# CouchProtato-TOP.net
KiCad netlist of a schematic drawn in EAGLE
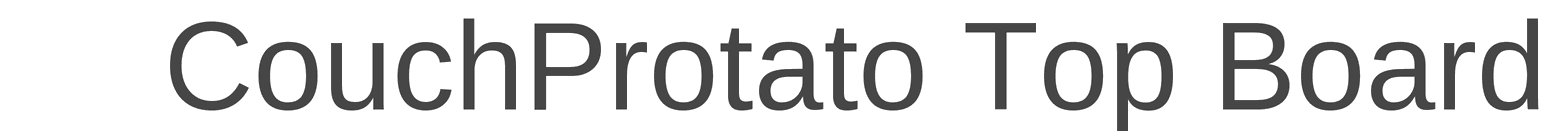
[diagram p0: schematic, sheet 1, part 1 of 2]
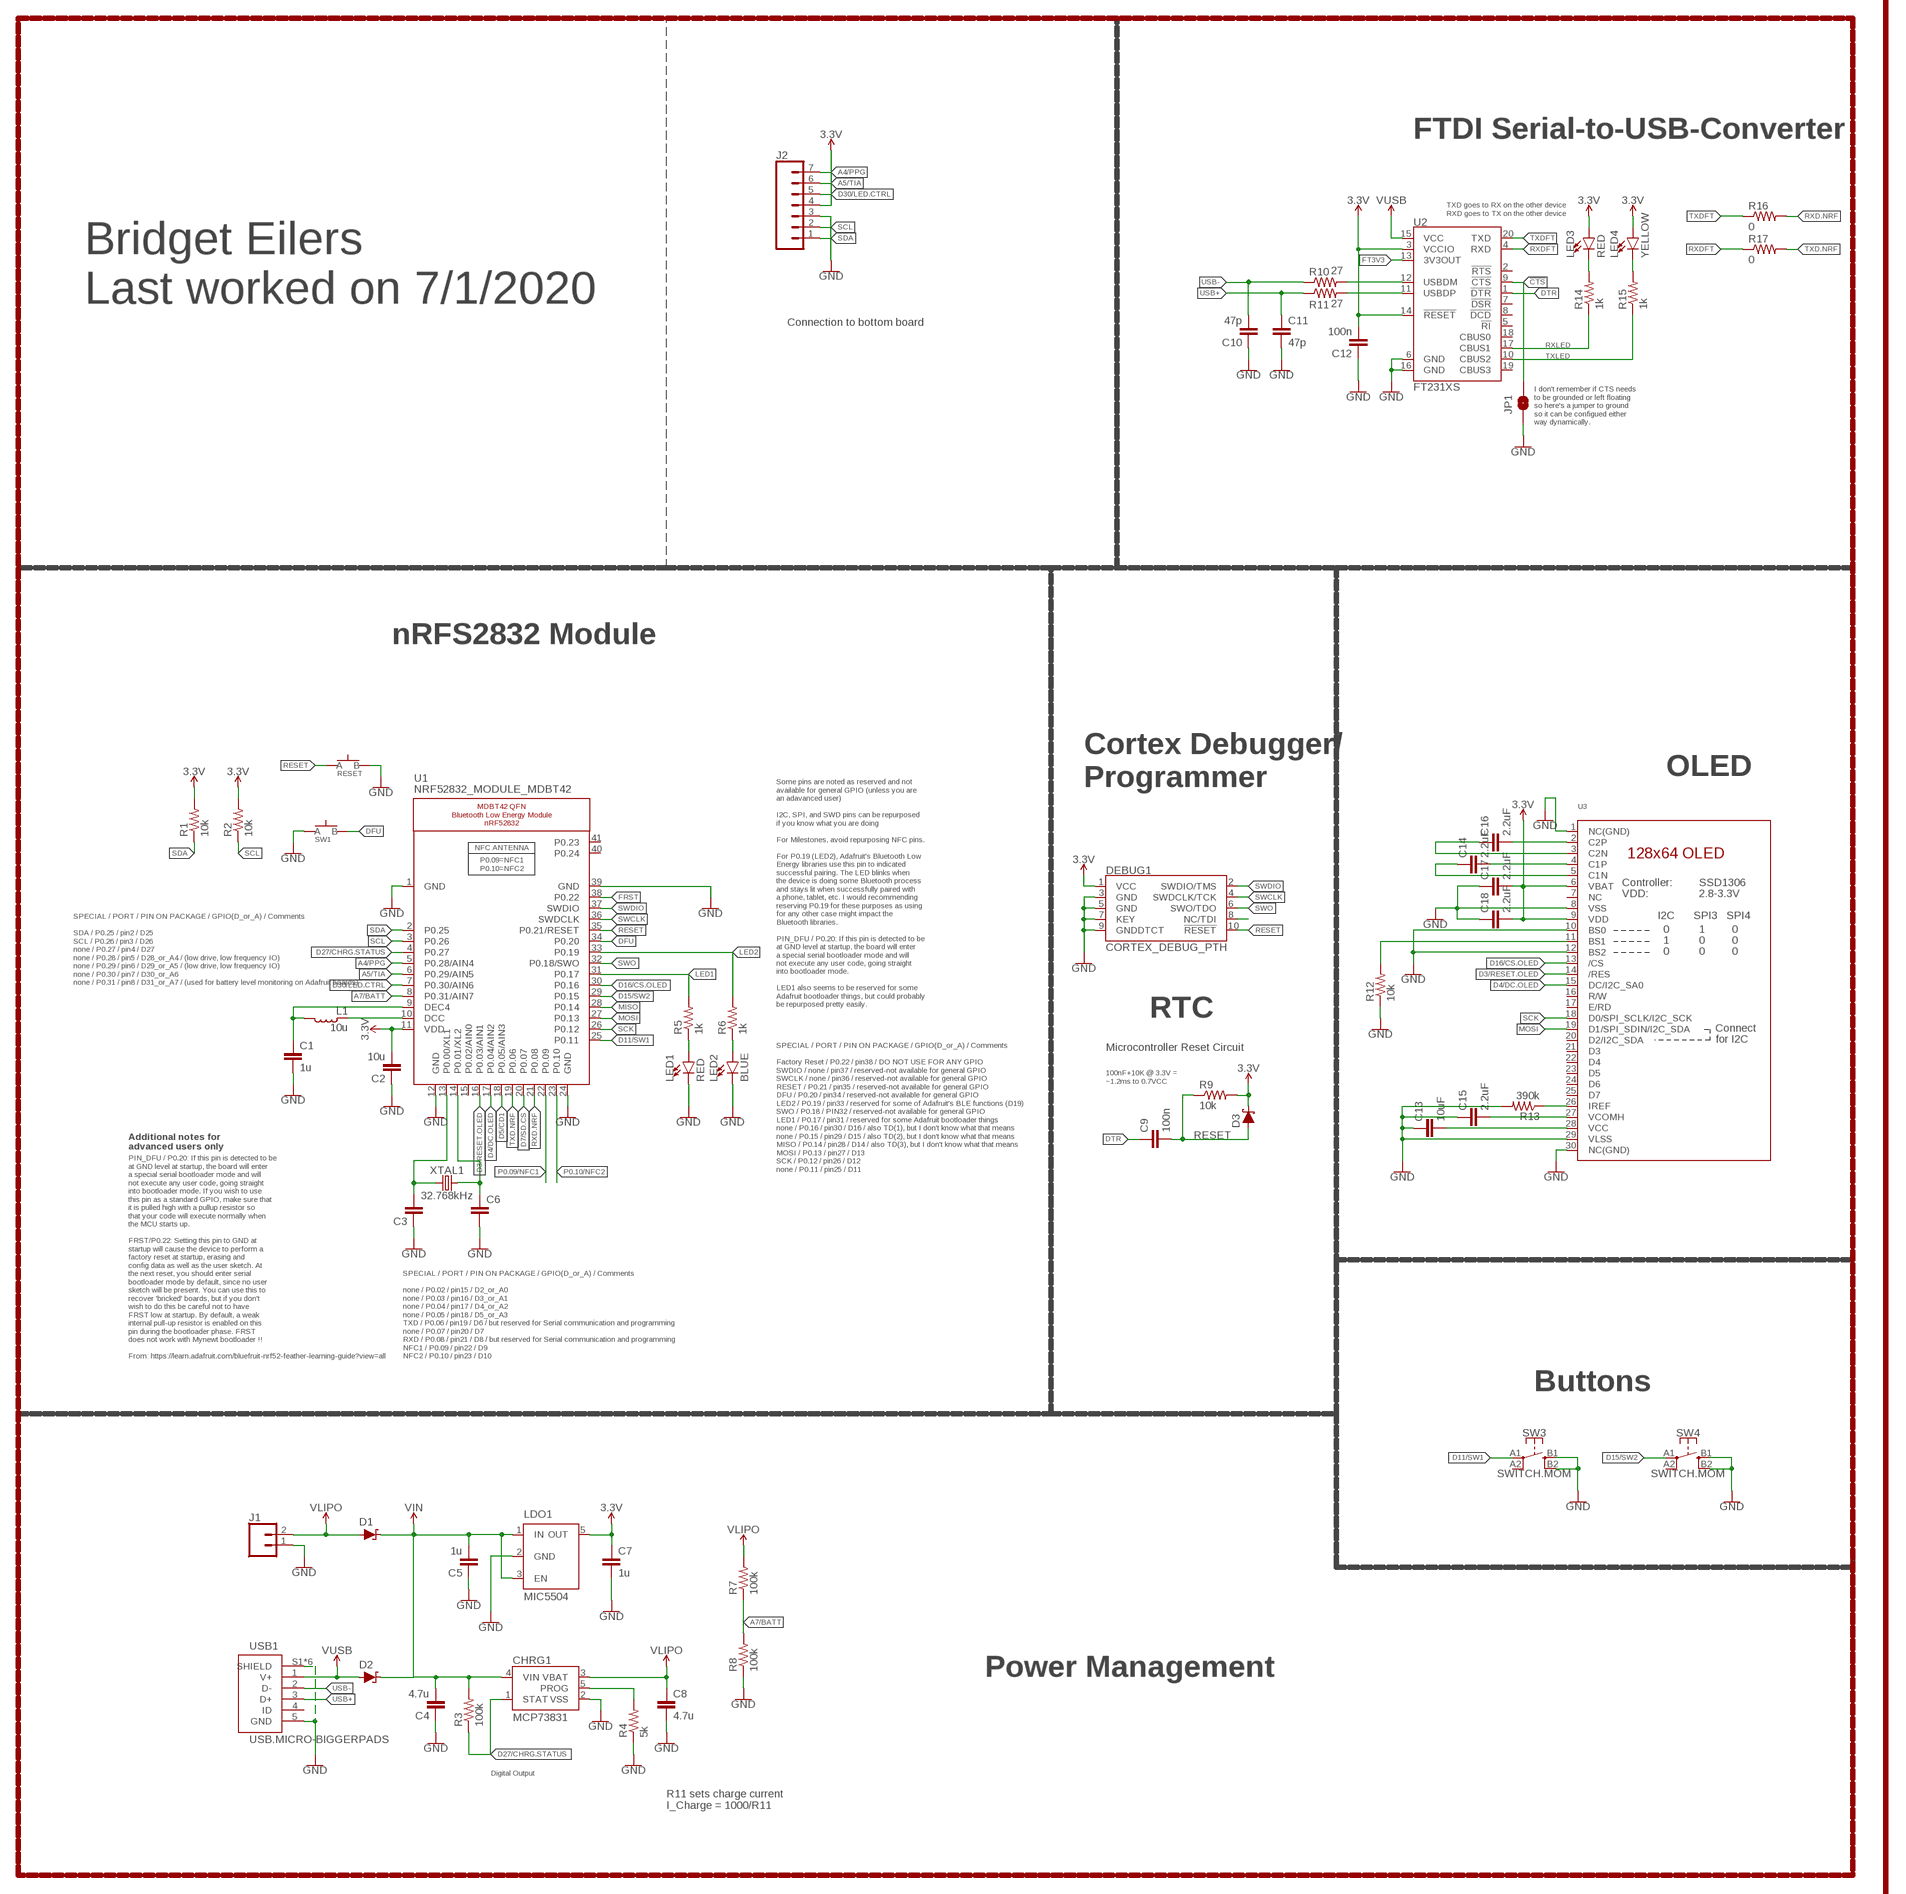
[diagram p1: schematic, sheet 1, part 2 of 2]

(export (version "E")
  (design (tool "Eeschema 10.0.6"))
  (components
    (comp (ref "C1")
      (value "1u")
      (footprint "eagle-import:C0603")
      (libsource (lib "eagle-import") (part "CAPACITOR0603"))
    )
    (comp (ref "C2")
      (value "10u")
      (footprint "eagle-import:C0805")
      (libsource (lib "eagle-import") (part "CAPACITOR0805"))
    )
    (comp (ref "C3")
      (value "CAPACITOR0603")
      (footprint "eagle-import:C0603")
      (libsource (lib "eagle-import") (part "CAPACITOR0603"))
    )
    (comp (ref "C4")
      (value "4.7u")
      (footprint "eagle-import:C0603")
      (libsource (lib "eagle-import") (part "CAPACITOR0603"))
    )
    (comp (ref "C5")
      (value "1u")
      (footprint "eagle-import:C0603")
      (libsource (lib "eagle-import") (part "CAPACITOR0603"))
    )
    (comp (ref "C6")
      (value "CAPACITOR0603")
      (footprint "eagle-import:C0603")
      (libsource (lib "eagle-import") (part "CAPACITOR0603"))
    )
    (comp (ref "C7")
      (value "1u")
      (footprint "eagle-import:C0603")
      (libsource (lib "eagle-import") (part "CAPACITOR0603"))
    )
    (comp (ref "C8")
      (value "4.7u")
      (footprint "eagle-import:C0603")
      (libsource (lib "eagle-import") (part "CAPACITOR0603"))
    )
    (comp (ref "C9")
      (value "100n")
      (footprint "eagle-import:C0603")
      (libsource (lib "eagle-import") (part "CAPACITOR0603"))
    )
    (comp (ref "C10")
      (value "47p")
      (footprint "eagle-import:C0603")
      (libsource (lib "eagle-import") (part "CAPACITOR0603"))
    )
    (comp (ref "C11")
      (value "47p")
      (footprint "eagle-import:C0603")
      (libsource (lib "eagle-import") (part "CAPACITOR0603"))
    )
    (comp (ref "C12")
      (value "100n")
      (footprint "eagle-import:C0603")
      (libsource (lib "eagle-import") (part "CAPACITOR0603"))
    )
    (comp (ref "C13")
      (value "10uF")
      (footprint "eagle-import:C0603")
      (libsource (lib "eagle-import") (part "CAPACITOR0603"))
    )
    (comp (ref "C14")
      (value "2.2uF")
      (footprint "eagle-import:C0402")
      (libsource (lib "eagle-import") (part "CAPACITOR0402"))
    )
    (comp (ref "C15")
      (value "2.2uF")
      (footprint "eagle-import:C0603")
      (libsource (lib "eagle-import") (part "CAPACITOR0603"))
    )
    (comp (ref "C16")
      (value "2.2uF")
      (footprint "eagle-import:C0402")
      (libsource (lib "eagle-import") (part "CAPACITOR0402"))
    )
    (comp (ref "C17")
      (value "2.2uF")
      (footprint "eagle-import:C0402")
      (libsource (lib "eagle-import") (part "CAPACITOR0402"))
    )
    (comp (ref "C18")
      (value "2.2uF")
      (footprint "eagle-import:C0402")
      (libsource (lib "eagle-import") (part "CAPACITOR0402"))
    )
    (comp (ref "CHRG1")
      (value "MCP73831")
      (footprint "eagle-import:SOT23-5")
      (libsource (lib "eagle-import") (part "MCP73831"))
    )
    (comp (ref "D1")
      (value "SCHOTTKY-USC")
      (footprint "eagle-import:USC")
      (libsource (lib "eagle-import") (part "SCHOTTKY-USC"))
    )
    (comp (ref "D2")
      (value "SCHOTTKY-USC")
      (footprint "eagle-import:USC")
      (libsource (lib "eagle-import") (part "SCHOTTKY-USC"))
    )
    (comp (ref "D3")
      (value "SCHOTTKY-USC")
      (footprint "eagle-import:USC")
      (libsource (lib "eagle-import") (part "SCHOTTKY-USC"))
    )
    (comp (ref "DEBUG1")
      (value "CORTEX_DEBUG_PTH")
      (footprint "eagle-import:2X5-PTH-1.27MM")
      (libsource (lib "eagle-import") (part "CORTEX_DEBUG_PTH"))
    )
    (comp (ref "J1")
      (value "CONN_02")
      (footprint "eagle-import:1X02")
      (libsource (lib "eagle-import") (part "CONN_02"))
    )
    (comp (ref "J2")
      (value "CONN_07-1.27MM")
      (footprint "eagle-import:1X07_1.27MM")
      (libsource (lib "eagle-import") (part "CONN_07-1.27MM"))
    )
    (comp (ref "JP1")
      (value "JUMPER-SMT_2_NO_SILK")
      (footprint "eagle-import:SMT-JUMPER_2_NO_SILK")
      (libsource (lib "eagle-import") (part "JUMPER-SMT_2_NO_SILK"))
    )
    (comp (ref "L1")
      (value "10u")
      (footprint "eagle-import:L0603")
      (libsource (lib "eagle-import") (part "INDUCTOR0603"))
    )
    (comp (ref "LDO1")
      (value "MIC5504")
      (footprint "eagle-import:SOT23-5")
      (libsource (lib "eagle-import") (part "MIC5504"))
    )
    (comp (ref "LED1")
      (value "RED")
      (footprint "eagle-import:LED-0603")
      (libsource (lib "eagle-import") (part "LED0603"))
    )
    (comp (ref "LED2")
      (value "BLUE")
      (footprint "eagle-import:LED-0603")
      (libsource (lib "eagle-import") (part "LED0603"))
    )
    (comp (ref "LED3")
      (value "RED")
      (footprint "eagle-import:LED-0603")
      (libsource (lib "eagle-import") (part "LED0603"))
    )
    (comp (ref "LED4")
      (value "YELLOW")
      (footprint "eagle-import:LED-0603")
      (libsource (lib "eagle-import") (part "LED0603"))
    )
    (comp (ref "R1")
      (value "10k")
      (footprint "eagle-import:R0603")
      (libsource (lib "eagle-import") (part "RESISTOR0603"))
    )
    (comp (ref "R2")
      (value "10k")
      (footprint "eagle-import:R0603")
      (libsource (lib "eagle-import") (part "RESISTOR0603"))
    )
    (comp (ref "R3")
      (value "100k")
      (footprint "eagle-import:R0603")
      (libsource (lib "eagle-import") (part "RESISTOR0603"))
    )
    (comp (ref "R4")
      (value "5k")
      (footprint "eagle-import:R0603")
      (libsource (lib "eagle-import") (part "RESISTOR0603"))
    )
    (comp (ref "R5")
      (value "1k")
      (footprint "eagle-import:R0603")
      (libsource (lib "eagle-import") (part "RESISTOR0603"))
    )
    (comp (ref "R6")
      (value "1k")
      (footprint "eagle-import:R0603")
      (libsource (lib "eagle-import") (part "RESISTOR0603"))
    )
    (comp (ref "R7")
      (value "100k")
      (footprint "eagle-import:R0603")
      (libsource (lib "eagle-import") (part "RESISTOR0603"))
    )
    (comp (ref "R8")
      (value "100k")
      (footprint "eagle-import:R0603")
      (libsource (lib "eagle-import") (part "RESISTOR0603"))
    )
    (comp (ref "R9")
      (value "10k")
      (footprint "eagle-import:R0603")
      (libsource (lib "eagle-import") (part "RESISTOR0603"))
    )
    (comp (ref "R10")
      (value "27")
      (footprint "eagle-import:R0603")
      (libsource (lib "eagle-import") (part "RESISTOR0603"))
    )
    (comp (ref "R11")
      (value "27")
      (footprint "eagle-import:R0603")
      (libsource (lib "eagle-import") (part "RESISTOR0603"))
    )
    (comp (ref "R12")
      (value "10k")
      (footprint "eagle-import:R0603")
      (libsource (lib "eagle-import") (part "RESISTOR0603"))
    )
    (comp (ref "R13")
      (value "390k")
      (footprint "eagle-import:R0603")
      (libsource (lib "eagle-import") (part "RESISTOR0603"))
    )
    (comp (ref "R14")
      (value "1k")
      (footprint "eagle-import:R0603")
      (libsource (lib "eagle-import") (part "RESISTOR0603"))
    )
    (comp (ref "R15")
      (value "1k")
      (footprint "eagle-import:R0603")
      (libsource (lib "eagle-import") (part "RESISTOR0603"))
    )
    (comp (ref "R16")
      (value "0")
      (footprint "eagle-import:R0603")
      (libsource (lib "eagle-import") (part "RESISTOR0603"))
    )
    (comp (ref "R17")
      (value "0")
      (footprint "eagle-import:R0603")
      (libsource (lib "eagle-import") (part "RESISTOR0603"))
    )
    (comp (ref "RESET")
      (value "SPST-PTS830GG140-COPY.1-3")
      (footprint "eagle-import:BUTTON-GULLWING")
      (libsource (lib "eagle-import") (part "SPST-PTS830GG140-COPY.1-3"))
    )
    (comp (ref "SW1")
      (value "SPST-PTS830GG140-COPY.1-3")
      (footprint "eagle-import:BUTTON-GULLWING")
      (libsource (lib "eagle-import") (part "SPST-PTS830GG140-COPY.1-3"))
    )
    (comp (ref "SW3")
      (value "SWITCH.MOM")
      (footprint "eagle-import:TACTILE_SWITCH_SMD_6.2MM_TALL")
      (libsource (lib "eagle-import") (part "SWITCH.MOM"))
    )
    (comp (ref "SW4")
      (value "SWITCH.MOM")
      (footprint "eagle-import:TACTILE_SWITCH_SMD_6.2MM_TALL")
      (libsource (lib "eagle-import") (part "SWITCH.MOM"))
    )
    (comp (ref "U1")
      (value "NRF52832_MODULE_MDBT42")
      (footprint "eagle-import:BLE_MODULE_RAYTAC_MDBT42")
      (libsource (lib "eagle-import") (part "NRF52832_MODULE_MDBT42"))
    )
    (comp (ref "U2")
      (value "FT231XS")
      (footprint "eagle-import:SSOP20_L")
      (libsource (lib "eagle-import") (part "FT231XS"))
    )
    (comp (ref "U3")
      (value "DISP_OLED_UG-2864HSWEG01-NO-WRAPAROUND")
      (footprint "eagle-import:UG-2864HSWEG01_0.96IN_NO-WRAPAROUND")
      (libsource (lib "eagle-import") (part "DISP_OLED_UG-2864HSWEG01-NO-WRAPAROUND"))
    )
    (comp (ref "USB1")
      (value "USB.MICRO-BIGGERPADS")
      (footprint "eagle-import:USB-MICRO-01.BIGGERPADS")
      (libsource (lib "eagle-import") (part "USB.MICRO-BIGGERPADS"))
    )
    (comp (ref "XTAL1")
      (value "32.768kHz")
      (footprint "eagle-import:2-SMD.NOLEAD.2.0MMTO1.2MM")
      (libsource (lib "eagle-import") (part "CRYSTALECS-.327-12.5-12-C-TR"))
    )
  )
  (nets
    (net (code "1") (name "/RXLED") (class "Default")
      (node (ref "R14") (pin "1") (pinfunction "1_1") (pintype "passive"))
      (node (ref "U2") (pin "17") (pinfunction "CBUS1_17") (pintype "bidirectional"))
    )
    (net (code "2") (name "/TXLED") (class "Default")
      (node (ref "R15") (pin "1") (pinfunction "1_1") (pintype "passive"))
      (node (ref "U2") (pin "10") (pinfunction "CBUS2_10") (pintype "bidirectional"))
    )
    (net (code "3") (name "/~{CTS}") (class "Default")
      (node (ref "JP1") (pin "2") (pinfunction "2_2") (pintype "passive"))
      (node (ref "U2") (pin "9") (pinfunction "~{CTS}_9") (pintype "bidirectional"))
    )
    (net (code "4") (name "3.3V") (class "Default")
      (node (ref "C12") (pin "2") (pinfunction "2_2") (pintype "passive"))
      (node (ref "C17") (pin "2") (pinfunction "2_2") (pintype "passive"))
      (node (ref "C18") (pin "2") (pinfunction "2_2") (pintype "passive"))
      (node (ref "C2") (pin "2") (pinfunction "2_2") (pintype "passive"))
      (node (ref "C7") (pin "1") (pinfunction "1_1") (pintype "passive"))
      (node (ref "D3") (pin "-") (pinfunction "C_-") (pintype "passive"))
      (node (ref "DEBUG1") (pin "1") (pinfunction "VCC_1") (pintype "bidirectional"))
      (node (ref "J2") (pin "4") (pinfunction "4_4") (pintype "passive"))
      (node (ref "LDO1") (pin "5") (pinfunction "OUT_5") (pintype "bidirectional"))
      (node (ref "LED3") (pin "A") (pinfunction "A_A") (pintype "passive"))
      (node (ref "LED4") (pin "A") (pinfunction "A_A") (pintype "passive"))
      (node (ref "R1") (pin "2") (pinfunction "2_2") (pintype "passive"))
      (node (ref "R2") (pin "2") (pinfunction "2_2") (pintype "passive"))
      (node (ref "R9") (pin "2") (pinfunction "2_2") (pintype "passive"))
      (node (ref "U1") (pin "11") (pinfunction "VDD_11") (pintype "bidirectional"))
      (node (ref "U2") (pin "14") (pinfunction "~{RESET}_14") (pintype "bidirectional"))
      (node (ref "U2") (pin "3") (pinfunction "VCCIO_3") (pintype "bidirectional"))
      (node (ref "U3") (pin "6") (pinfunction "VBAT_6") (pintype "input"))
      (node (ref "U3") (pin "9") (pinfunction "VDD_9") (pintype "power_in"))
    )
    (net (code "5") (name "A4{slash}PPG") (class "Default")
      (node (ref "J2") (pin "7") (pinfunction "7_7") (pintype "passive"))
      (node (ref "U1") (pin "5") (pinfunction "P0.28/AIN4_5") (pintype "bidirectional"))
    )
    (net (code "6") (name "A5{slash}TIA") (class "Default")
      (node (ref "J2") (pin "6") (pinfunction "6_6") (pintype "passive"))
      (node (ref "U1") (pin "6") (pinfunction "P0.29/AIN5_6") (pintype "bidirectional"))
    )
    (net (code "7") (name "A7{slash}BATT") (class "Default")
      (node (ref "R7") (pin "1") (pinfunction "1_1") (pintype "passive"))
      (node (ref "R8") (pin "2") (pinfunction "2_2") (pintype "passive"))
      (node (ref "U1") (pin "8") (pinfunction "P0.31/AIN7_8") (pintype "bidirectional"))
    )
    (net (code "8") (name "D3{slash}RESET.OLED") (class "Default")
      (node (ref "U1") (pin "16") (pinfunction "P0.03/AIN1_16") (pintype "bidirectional"))
      (node (ref "U3") (pin "14") (pinfunction "/RES_14") (pintype "input"))
    )
    (net (code "9") (name "D4{slash}DC.OLED") (class "Default")
      (node (ref "U1") (pin "17") (pinfunction "P0.04/AIN2_17") (pintype "bidirectional"))
      (node (ref "U3") (pin "15") (pinfunction "DC/I2C_SA0_15") (pintype "input"))
    )
    (net (code "10") (name "D5{slash}CD1") (class "Default")
      (node (ref "U1") (pin "18") (pinfunction "P0.05/AIN3_18") (pintype "bidirectional"))
    )
    (net (code "11") (name "D7{slash}SD.CS") (class "Default")
      (node (ref "U1") (pin "20") (pinfunction "P0.07_20") (pintype "bidirectional"))
    )
    (net (code "12") (name "D11{slash}SW1") (class "Default")
      (node (ref "SW3") (pin "A1") (pinfunction "1_A1") (pintype "passive"))
      (node (ref "U1") (pin "25") (pinfunction "P0.11_25") (pintype "bidirectional"))
    )
    (net (code "13") (name "D15{slash}SW2") (class "Default")
      (node (ref "SW4") (pin "A1") (pinfunction "1_A1") (pintype "passive"))
      (node (ref "U1") (pin "29") (pinfunction "P0.15_29") (pintype "bidirectional"))
    )
    (net (code "14") (name "D16{slash}CS.OLED") (class "Default")
      (node (ref "U1") (pin "30") (pinfunction "P0.16_30") (pintype "bidirectional"))
      (node (ref "U3") (pin "13") (pinfunction "/CS_13") (pintype "input"))
    )
    (net (code "15") (name "D27{slash}CHRG.STATUS") (class "Default")
      (node (ref "CHRG1") (pin "1") (pinfunction "STAT_1") (pintype "output"))
      (node (ref "R3") (pin "1") (pinfunction "1_1") (pintype "passive"))
      (node (ref "U1") (pin "4") (pinfunction "P0.27_4") (pintype "bidirectional"))
    )
    (net (code "16") (name "D30{slash}LED.CTRL") (class "Default")
      (node (ref "J2") (pin "5") (pinfunction "5_5") (pintype "passive"))
      (node (ref "U1") (pin "7") (pinfunction "P0.30/AIN6_7") (pintype "bidirectional"))
    )
    (net (code "17") (name "DFU") (class "Default")
      (node (ref "SW1") (pin "3") (pinfunction "B_3") (pintype "bidirectional"))
      (node (ref "U1") (pin "34") (pinfunction "P0.20_34") (pintype "bidirectional"))
    )
    (net (code "18") (name "DTR") (class "Default")
      (node (ref "C9") (pin "1") (pinfunction "1_1") (pintype "passive"))
      (node (ref "U2") (pin "1") (pinfunction "~{DTR}_1") (pintype "bidirectional"))
    )
    (net (code "19") (name "FRST") (class "Default")
      (node (ref "U1") (pin "38") (pinfunction "P0.22_38") (pintype "bidirectional"))
    )
    (net (code "20") (name "FT3V3") (class "Default")
      (node (ref "U2") (pin "13") (pinfunction "3V3OUT_13") (pintype "bidirectional"))
    )
    (net (code "21") (name "GND") (class "Default")
      (node (ref "C1") (pin "2") (pinfunction "2_2") (pintype "passive"))
      (node (ref "C10") (pin "1") (pinfunction "1_1") (pintype "passive"))
      (node (ref "C11") (pin "2") (pinfunction "2_2") (pintype "passive"))
      (node (ref "C12") (pin "1") (pinfunction "1_1") (pintype "passive"))
      (node (ref "C13") (pin "1") (pinfunction "1_1") (pintype "passive"))
      (node (ref "C15") (pin "1") (pinfunction "1_1") (pintype "passive"))
      (node (ref "C17") (pin "1") (pinfunction "1_1") (pintype "passive"))
      (node (ref "C18") (pin "1") (pinfunction "1_1") (pintype "passive"))
      (node (ref "C2") (pin "1") (pinfunction "1_1") (pintype "passive"))
      (node (ref "C3") (pin "1") (pinfunction "1_1") (pintype "passive"))
      (node (ref "C4") (pin "1") (pinfunction "1_1") (pintype "passive"))
      (node (ref "C5") (pin "1") (pinfunction "1_1") (pintype "passive"))
      (node (ref "C6") (pin "2") (pinfunction "2_2") (pintype "passive"))
      (node (ref "C7") (pin "2") (pinfunction "2_2") (pintype "passive"))
      (node (ref "C8") (pin "2") (pinfunction "2_2") (pintype "passive"))
      (node (ref "CHRG1") (pin "2") (pinfunction "VSS_2") (pintype "power_in"))
      (node (ref "DEBUG1") (pin "3") (pinfunction "GND_3") (pintype "bidirectional"))
      (node (ref "DEBUG1") (pin "5") (pinfunction "GND_5") (pintype "bidirectional"))
      (node (ref "DEBUG1") (pin "7") (pinfunction "KEY_7") (pintype "bidirectional"))
      (node (ref "DEBUG1") (pin "9") (pinfunction "GNDDTCT_9") (pintype "bidirectional"))
      (node (ref "J1") (pin "1") (pinfunction "1_1") (pintype "passive"))
      (node (ref "J2") (pin "3") (pinfunction "3_3") (pintype "passive"))
      (node (ref "JP1") (pin "1") (pinfunction "1_1") (pintype "passive"))
      (node (ref "LDO1") (pin "2") (pinfunction "GND_2") (pintype "bidirectional"))
      (node (ref "LED1") (pin "C") (pinfunction "C_C") (pintype "passive"))
      (node (ref "LED2") (pin "C") (pinfunction "C_C") (pintype "passive"))
      (node (ref "R12") (pin "1") (pinfunction "1_1") (pintype "passive"))
      (node (ref "R13") (pin "2") (pinfunction "2_2") (pintype "passive"))
      (node (ref "R4") (pin "1") (pinfunction "1_1") (pintype "passive"))
      (node (ref "R8") (pin "1") (pinfunction "1_1") (pintype "passive"))
      (node (ref "RESET") (pin "3") (pinfunction "B_3") (pintype "bidirectional"))
      (node (ref "SW1") (pin "1") (pinfunction "A_1") (pintype "bidirectional"))
      (node (ref "SW3") (pin "B1") (pinfunction "3_B1") (pintype "passive"))
      (node (ref "SW3") (pin "B2") (pinfunction "4_B2") (pintype "passive"))
      (node (ref "SW4") (pin "B1") (pinfunction "3_B1") (pintype "passive"))
      (node (ref "SW4") (pin "B2") (pinfunction "4_B2") (pintype "passive"))
      (node (ref "U1") (pin "1") (pinfunction "GND_1") (pintype "bidirectional"))
      (node (ref "U1") (pin "12") (pinfunction "GND_12") (pintype "bidirectional"))
      (node (ref "U1") (pin "24") (pinfunction "GND_24") (pintype "bidirectional"))
      (node (ref "U1") (pin "39") (pinfunction "GND_39") (pintype "bidirectional"))
      (node (ref "U2") (pin "16") (pinfunction "GND_16") (pintype "bidirectional"))
      (node (ref "U2") (pin "6") (pinfunction "GND_6") (pintype "bidirectional"))
      (node (ref "U3") (pin "1") (pinfunction "NC(GND)_1") (pintype "input"))
      (node (ref "U3") (pin "10") (pinfunction "BS0_10") (pintype "input"))
      (node (ref "U3") (pin "12") (pinfunction "BS2_12") (pintype "input"))
      (node (ref "U3") (pin "29") (pinfunction "VLSS_29") (pintype "power_in"))
      (node (ref "U3") (pin "30") (pinfunction "NC(GND)_30") (pintype "input"))
      (node (ref "U3") (pin "8") (pinfunction "VSS_8") (pintype "power_in"))
      (node (ref "USB1") (pin "5") (pinfunction "GND_5") (pintype "bidirectional"))
      (node (ref "USB1") (pin "S1") (pinfunction "SHIELD_S1") (pintype "bidirectional"))
      (node (ref "USB1") (pin "S2") (pinfunction "SHIELD_S2") (pintype "bidirectional"))
      (node (ref "USB1") (pin "S3") (pinfunction "SHIELD_S3") (pintype "bidirectional"))
      (node (ref "USB1") (pin "S4") (pinfunction "SHIELD_S4") (pintype "bidirectional"))
      (node (ref "USB1") (pin "S5") (pinfunction "SHIELD_S5") (pintype "bidirectional"))
      (node (ref "USB1") (pin "S6") (pinfunction "SHIELD_S6") (pintype "bidirectional"))
    )
    (net (code "22") (name "LED1") (class "Default")
      (node (ref "R5") (pin "2") (pinfunction "2_2") (pintype "passive"))
      (node (ref "U1") (pin "31") (pinfunction "P0.17_31") (pintype "bidirectional"))
    )
    (net (code "23") (name "LED2") (class "Default")
      (node (ref "R6") (pin "2") (pinfunction "2_2") (pintype "passive"))
      (node (ref "U1") (pin "33") (pinfunction "P0.19_33") (pintype "bidirectional"))
    )
    (net (code "24") (name "MISO") (class "Default")
      (node (ref "U1") (pin "28") (pinfunction "P0.14_28") (pintype "bidirectional"))
    )
    (net (code "25") (name "MOSI") (class "Default")
      (node (ref "U1") (pin "27") (pinfunction "P0.13_27") (pintype "bidirectional"))
      (node (ref "U3") (pin "19") (pinfunction "D1/SPI_SDIN/I2C_SDA_19") (pintype "bidirectional"))
    )
    (net (code "26") (name "Net-(CHRG1-PROG)") (class "Default")
      (node (ref "CHRG1") (pin "5") (pinfunction "PROG_5") (pintype "input"))
      (node (ref "R4") (pin "2") (pinfunction "2_2") (pintype "passive"))
    )
    (net (code "27") (name "Net-(LED1-PadA)") (class "Default")
      (node (ref "LED1") (pin "A") (pinfunction "A_A") (pintype "passive"))
      (node (ref "R5") (pin "1") (pinfunction "1_1") (pintype "passive"))
    )
    (net (code "28") (name "Net-(LED2-PadA)") (class "Default")
      (node (ref "LED2") (pin "A") (pinfunction "A_A") (pintype "passive"))
      (node (ref "R6") (pin "1") (pinfunction "1_1") (pintype "passive"))
    )
    (net (code "29") (name "Net-(LED3-PadC)") (class "Default")
      (node (ref "LED3") (pin "C") (pinfunction "C_C") (pintype "passive"))
      (node (ref "R14") (pin "2") (pinfunction "2_2") (pintype "passive"))
    )
    (net (code "30") (name "Net-(LED4-PadC)") (class "Default")
      (node (ref "LED4") (pin "C") (pinfunction "C_C") (pintype "passive"))
      (node (ref "R15") (pin "2") (pinfunction "2_2") (pintype "passive"))
    )
    (net (code "31") (name "Net-(U1-DCC)") (class "Default")
      (node (ref "L1") (pin "1") (pinfunction "1_1") (pintype "passive"))
      (node (ref "U1") (pin "10") (pinfunction "DCC_10") (pintype "bidirectional"))
    )
    (net (code "32") (name "Net-(U1-DEC4)") (class "Default")
      (node (ref "C1") (pin "1") (pinfunction "1_1") (pintype "passive"))
      (node (ref "L1") (pin "2") (pinfunction "2_2") (pintype "passive"))
      (node (ref "U1") (pin "9") (pinfunction "DEC4_9") (pintype "bidirectional"))
    )
    (net (code "33") (name "Net-(U1-P0.00{slash}XL1)") (class "Default")
      (node (ref "C3") (pin "2") (pinfunction "2_2") (pintype "passive"))
      (node (ref "U1") (pin "13") (pinfunction "P0.00/XL1_13") (pintype "bidirectional"))
      (node (ref "XTAL1") (pin "P$1") (pinfunction "1_P$1") (pintype "passive"))
    )
    (net (code "34") (name "Net-(U1-P0.01{slash}XL2)") (class "Default")
      (node (ref "C6") (pin "1") (pinfunction "1_1") (pintype "passive"))
      (node (ref "U1") (pin "14") (pinfunction "P0.01/XL2_14") (pintype "bidirectional"))
      (node (ref "XTAL1") (pin "P$2") (pinfunction "2_P$2") (pintype "passive"))
    )
    (net (code "35") (name "Net-(U2-USBDM)") (class "Default")
      (node (ref "R10") (pin "2") (pinfunction "2_2") (pintype "passive"))
      (node (ref "U2") (pin "12") (pinfunction "USBDM_12") (pintype "bidirectional"))
    )
    (net (code "36") (name "Net-(U2-USBDP)") (class "Default")
      (node (ref "R11") (pin "2") (pinfunction "2_2") (pintype "passive"))
      (node (ref "U2") (pin "11") (pinfunction "USBDP_11") (pintype "bidirectional"))
    )
    (net (code "37") (name "Net-(U3-BS1)") (class "Default")
      (node (ref "R12") (pin "2") (pinfunction "2_2") (pintype "passive"))
      (node (ref "U3") (pin "11") (pinfunction "BS1_11") (pintype "input"))
    )
    (net (code "38") (name "Net-(U3-C1N)") (class "Default")
      (node (ref "C14") (pin "1") (pinfunction "1_1") (pintype "passive"))
      (node (ref "U3") (pin "5") (pinfunction "C1N_5") (pintype "input"))
    )
    (net (code "39") (name "Net-(U3-C1P)") (class "Default")
      (node (ref "C14") (pin "2") (pinfunction "2_2") (pintype "passive"))
      (node (ref "U3") (pin "4") (pinfunction "C1P_4") (pintype "input"))
    )
    (net (code "40") (name "Net-(U3-C2N)") (class "Default")
      (node (ref "C16") (pin "1") (pinfunction "1_1") (pintype "passive"))
      (node (ref "U3") (pin "3") (pinfunction "C2N_3") (pintype "input"))
    )
    (net (code "41") (name "Net-(U3-C2P)") (class "Default")
      (node (ref "C16") (pin "2") (pinfunction "2_2") (pintype "passive"))
      (node (ref "U3") (pin "2") (pinfunction "C2P_2") (pintype "input"))
    )
    (net (code "42") (name "Net-(U3-IREF)") (class "Default")
      (node (ref "R13") (pin "1") (pinfunction "1_1") (pintype "passive"))
      (node (ref "U3") (pin "26") (pinfunction "IREF_26") (pintype "input"))
    )
    (net (code "43") (name "Net-(U3-VCC)") (class "Default")
      (node (ref "C13") (pin "2") (pinfunction "2_2") (pintype "passive"))
      (node (ref "U3") (pin "28") (pinfunction "VCC_28") (pintype "power_in"))
    )
    (net (code "44") (name "Net-(U3-VCOMH)") (class "Default")
      (node (ref "C15") (pin "2") (pinfunction "2_2") (pintype "passive"))
      (node (ref "U3") (pin "27") (pinfunction "VCOMH_27") (pintype "output"))
    )
    (net (code "45") (name "P0.09{slash}NFC1") (class "Default")
      (node (ref "U1") (pin "22") (pinfunction "P0.09_22") (pintype "bidirectional"))
    )
    (net (code "46") (name "P0.10{slash}NFC2") (class "Default")
      (node (ref "U1") (pin "23") (pinfunction "P0.10_23") (pintype "bidirectional"))
    )
    (net (code "47") (name "RESET") (class "Default")
      (node (ref "C9") (pin "2") (pinfunction "2_2") (pintype "passive"))
      (node (ref "D3") (pin "+") (pinfunction "A_+") (pintype "passive"))
      (node (ref "DEBUG1") (pin "10") (pinfunction "~{RESET}_10") (pintype "bidirectional"))
      (node (ref "R9") (pin "1") (pinfunction "1_1") (pintype "passive"))
      (node (ref "RESET") (pin "1") (pinfunction "A_1") (pintype "bidirectional"))
      (node (ref "U1") (pin "35") (pinfunction "P0.21/RESET_35") (pintype "bidirectional"))
    )
    (net (code "48") (name "RXD.NRF") (class "Default")
      (node (ref "R16") (pin "2") (pinfunction "2_2") (pintype "passive"))
      (node (ref "U1") (pin "21") (pinfunction "P0.08_21") (pintype "bidirectional"))
    )
    (net (code "49") (name "RXDFT") (class "Default")
      (node (ref "R17") (pin "1") (pinfunction "1_1") (pintype "passive"))
      (node (ref "U2") (pin "4") (pinfunction "RXD_4") (pintype "bidirectional"))
    )
    (net (code "50") (name "SCK") (class "Default")
      (node (ref "U1") (pin "26") (pinfunction "P0.12_26") (pintype "bidirectional"))
      (node (ref "U3") (pin "18") (pinfunction "D0/SPI_SCLK/I2C_SCK_18") (pintype "bidirectional"))
    )
    (net (code "51") (name "SCL") (class "Default")
      (node (ref "J2") (pin "2") (pinfunction "2_2") (pintype "passive"))
      (node (ref "R2") (pin "1") (pinfunction "1_1") (pintype "passive"))
      (node (ref "U1") (pin "3") (pinfunction "P0.26_3") (pintype "bidirectional"))
    )
    (net (code "52") (name "SDA") (class "Default")
      (node (ref "J2") (pin "1") (pinfunction "1_1") (pintype "passive"))
      (node (ref "R1") (pin "1") (pinfunction "1_1") (pintype "passive"))
      (node (ref "U1") (pin "2") (pinfunction "P0.25_2") (pintype "bidirectional"))
    )
    (net (code "53") (name "SWCLK") (class "Default")
      (node (ref "DEBUG1") (pin "4") (pinfunction "SWDCLK/TCK_4") (pintype "bidirectional"))
      (node (ref "U1") (pin "36") (pinfunction "SWDCLK_36") (pintype "bidirectional"))
    )
    (net (code "54") (name "SWDIO") (class "Default")
      (node (ref "DEBUG1") (pin "2") (pinfunction "SWDIO/TMS_2") (pintype "bidirectional"))
      (node (ref "U1") (pin "37") (pinfunction "SWDIO_37") (pintype "bidirectional"))
    )
    (net (code "55") (name "SWO") (class "Default")
      (node (ref "DEBUG1") (pin "6") (pinfunction "SWO/TDO_6") (pintype "bidirectional"))
      (node (ref "U1") (pin "32") (pinfunction "P0.18/SWO_32") (pintype "bidirectional"))
    )
    (net (code "56") (name "TXD.NRF") (class "Default")
      (node (ref "R17") (pin "2") (pinfunction "2_2") (pintype "passive"))
      (node (ref "U1") (pin "19") (pinfunction "P0.06_19") (pintype "bidirectional"))
    )
    (net (code "57") (name "TXDFT") (class "Default")
      (node (ref "R16") (pin "1") (pinfunction "1_1") (pintype "passive"))
      (node (ref "U2") (pin "20") (pinfunction "TXD_20") (pintype "bidirectional"))
    )
    (net (code "58") (name "USB+") (class "Default")
      (node (ref "C11") (pin "1") (pinfunction "1_1") (pintype "passive"))
      (node (ref "R11") (pin "1") (pinfunction "1_1") (pintype "passive"))
      (node (ref "USB1") (pin "3") (pinfunction "D+_3") (pintype "bidirectional"))
    )
    (net (code "59") (name "USB-") (class "Default")
      (node (ref "C10") (pin "2") (pinfunction "2_2") (pintype "passive"))
      (node (ref "R10") (pin "1") (pinfunction "1_1") (pintype "passive"))
      (node (ref "USB1") (pin "2") (pinfunction "D-_2") (pintype "bidirectional"))
    )
    (net (code "60") (name "VIN") (class "Default")
      (node (ref "C4") (pin "2") (pinfunction "2_2") (pintype "passive"))
      (node (ref "C5") (pin "2") (pinfunction "2_2") (pintype "passive"))
      (node (ref "CHRG1") (pin "4") (pinfunction "VIN_4") (pintype "power_in"))
      (node (ref "D1") (pin "-") (pinfunction "C_-") (pintype "passive"))
      (node (ref "D2") (pin "-") (pinfunction "C_-") (pintype "passive"))
      (node (ref "LDO1") (pin "1") (pinfunction "IN_1") (pintype "bidirectional"))
      (node (ref "LDO1") (pin "3") (pinfunction "EN_3") (pintype "bidirectional"))
      (node (ref "R3") (pin "2") (pinfunction "2_2") (pintype "passive"))
    )
    (net (code "61") (name "VLIPO") (class "Default")
      (node (ref "C8") (pin "1") (pinfunction "1_1") (pintype "passive"))
      (node (ref "CHRG1") (pin "3") (pinfunction "VBAT_3") (pintype "power_in"))
      (node (ref "D1") (pin "+") (pinfunction "A_+") (pintype "passive"))
      (node (ref "J1") (pin "2") (pinfunction "2_2") (pintype "passive"))
      (node (ref "R7") (pin "2") (pinfunction "2_2") (pintype "passive"))
    )
    (net (code "62") (name "VUSB") (class "Default")
      (node (ref "D2") (pin "+") (pinfunction "A_+") (pintype "passive"))
      (node (ref "U2") (pin "15") (pinfunction "VCC_15") (pintype "bidirectional"))
      (node (ref "USB1") (pin "1") (pinfunction "V+_1") (pintype "bidirectional"))
    )
    (net (code "63") (name "unconnected-(DEBUG1-NC{slash}TDI-Pad8)") (class "Default")
      (node (ref "DEBUG1") (pin "8") (pinfunction "NC/TDI_8") (pintype "bidirectional"))
    )
    (net (code "64") (name "unconnected-(SW3-2-PadA2)") (class "Default")
      (node (ref "SW3") (pin "A2") (pinfunction "2_A2") (pintype "passive"))
    )
    (net (code "65") (name "unconnected-(SW4-2-PadA2)") (class "Default")
      (node (ref "SW4") (pin "A2") (pinfunction "2_A2") (pintype "passive"))
    )
    (net (code "66") (name "unconnected-(U1-P0.02{slash}AIN0-Pad15)") (class "Default")
      (node (ref "U1") (pin "15") (pinfunction "P0.02/AIN0_15") (pintype "bidirectional"))
    )
    (net (code "67") (name "unconnected-(U1-P0.23-Pad41)") (class "Default")
      (node (ref "U1") (pin "41") (pinfunction "P0.23_41") (pintype "bidirectional"))
    )
    (net (code "68") (name "unconnected-(U1-P0.24-Pad40)") (class "Default")
      (node (ref "U1") (pin "40") (pinfunction "P0.24_40") (pintype "bidirectional"))
    )
    (net (code "69") (name "unconnected-(U2-CBUS0-Pad18)") (class "Default")
      (node (ref "U2") (pin "18") (pinfunction "CBUS0_18") (pintype "bidirectional"))
    )
    (net (code "70") (name "unconnected-(U2-CBUS3-Pad19)") (class "Default")
      (node (ref "U2") (pin "19") (pinfunction "CBUS3_19") (pintype "bidirectional"))
    )
    (net (code "71") (name "unconnected-(U2-~{DCD}-Pad8)") (class "Default")
      (node (ref "U2") (pin "8") (pinfunction "~{DCD}_8") (pintype "bidirectional"))
    )
    (net (code "72") (name "unconnected-(U2-~{DSR}-Pad7)") (class "Default")
      (node (ref "U2") (pin "7") (pinfunction "~{DSR}_7") (pintype "bidirectional"))
    )
    (net (code "73") (name "unconnected-(U2-~{RI}-Pad5)") (class "Default")
      (node (ref "U2") (pin "5") (pinfunction "~{RI}_5") (pintype "bidirectional"))
    )
    (net (code "74") (name "unconnected-(U2-~{RTS}-Pad2)") (class "Default")
      (node (ref "U2") (pin "2") (pinfunction "~{RTS}_2") (pintype "bidirectional"))
    )
    (net (code "75") (name "unconnected-(U3-D2{slash}I2C_SDA-Pad20)") (class "Default")
      (node (ref "U3") (pin "20") (pinfunction "D2/I2C_SDA_20") (pintype "bidirectional"))
    )
    (net (code "76") (name "unconnected-(U3-D3-Pad21)") (class "Default")
      (node (ref "U3") (pin "21") (pinfunction "D3_21") (pintype "bidirectional"))
    )
    (net (code "77") (name "unconnected-(U3-D4-Pad22)") (class "Default")
      (node (ref "U3") (pin "22") (pinfunction "D4_22") (pintype "bidirectional"))
    )
    (net (code "78") (name "unconnected-(U3-D5-Pad23)") (class "Default")
      (node (ref "U3") (pin "23") (pinfunction "D5_23") (pintype "bidirectional"))
    )
    (net (code "79") (name "unconnected-(U3-D6-Pad24)") (class "Default")
      (node (ref "U3") (pin "24") (pinfunction "D6_24") (pintype "bidirectional"))
    )
    (net (code "80") (name "unconnected-(U3-D7-Pad25)") (class "Default")
      (node (ref "U3") (pin "25") (pinfunction "D7_25") (pintype "bidirectional"))
    )
    (net (code "81") (name "unconnected-(U3-E{slash}RD-Pad17)") (class "Default")
      (node (ref "U3") (pin "17") (pinfunction "E/RD_17") (pintype "input"))
    )
    (net (code "82") (name "unconnected-(U3-NC-Pad7)") (class "Default")
      (node (ref "U3") (pin "7") (pinfunction "NC_7") (pintype "no_connect"))
    )
    (net (code "83") (name "unconnected-(U3-R{slash}W-Pad16)") (class "Default")
      (node (ref "U3") (pin "16") (pinfunction "R/W_16") (pintype "input"))
    )
    (net (code "84") (name "unconnected-(USB1-ID-Pad4)") (class "Default")
      (node (ref "USB1") (pin "4") (pinfunction "ID_4") (pintype "bidirectional"))
    )
  )
)
